# CSI2-ZCU106-EVK-2_Rev01.net
KiCad netlist of a schematic drawn in Altium Designer
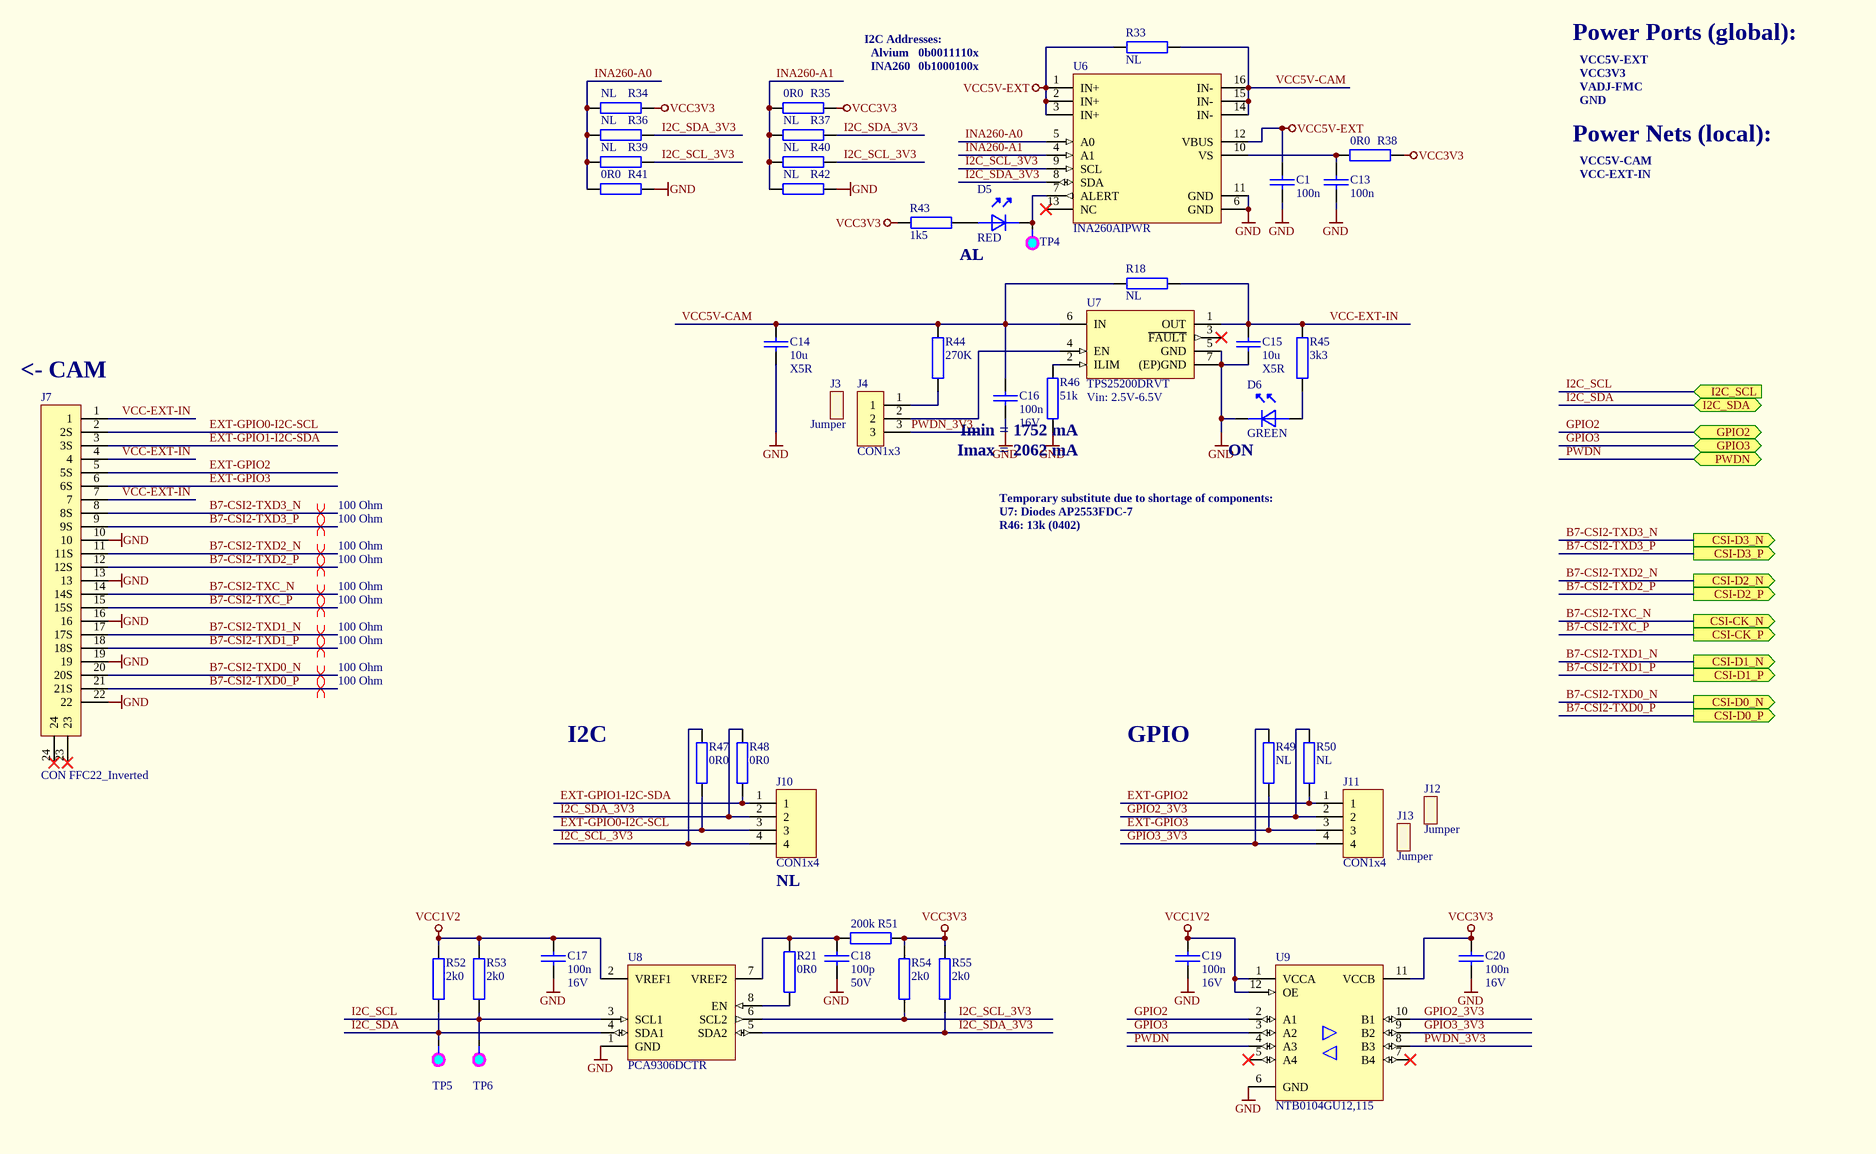
[diagram p0: CSI2-ZCU106-EVK-2_Rev01.SchDoc]

(export (version "E")
  (design (tool "Eeschema 10.0.6"))
  (components
    (comp (ref "C1")
      (value "100n")
      (footprint "C-0402_0.55")
      (description "Capacitor Ceramic SMD/0402/16V/X7R/10%")
      (fields (field (name "KHK PART NUMBER") "K8340114") (field (name "MANUFACTURER") "several"))
      (libsource (lib "AVT_KHK_Lib") (part "C 100N 10% 16V X7R 402"))
    )
    (comp (ref "C13")
      (value "100n")
      (footprint "C-0402_0.55")
      (description "Capacitor Ceramic SMD/0402/16V/X7R/10%")
      (fields (field (name "KHK PART NUMBER") "K8340114") (field (name "MANUFACTURER") "several"))
      (libsource (lib "AVT_KHK_Lib") (part "C 100N 10% 16V X7R 402"))
    )
    (comp (ref "C14")
      (value "10u")
      (footprint "C-0805_1.4")
      (description "Capacitor Ceramic SMD/0805/16V/X5R/10%")
      (fields
        (field (name "KHK PART NUMBER") "K8340151")
        (field (name "MANUFACTURER") "several")
        (field (name "DIELECTRIC") "X5R")
      )
      (libsource (lib "AVT_KHK_Lib") (part "C 10U 16V X5R 0805"))
    )
    (comp (ref "C15")
      (value "10u")
      (footprint "C-0805_1.4")
      (description "Capacitor Ceramic SMD/0805/16V/X5R/10%")
      (fields
        (field (name "KHK PART NUMBER") "K8340151")
        (field (name "MANUFACTURER") "several")
        (field (name "DIELECTRIC") "X5R")
      )
      (libsource (lib "AVT_KHK_Lib") (part "C 10U 16V X5R 0805"))
    )
    (comp (ref "C16")
      (value "100n")
      (footprint "C-0402_0.55")
      (description "Capacitor Ceramic SMD/0402/16V/X7R/10%")
      (fields
        (field (name "KHK PART NUMBER") "K8340114")
        (field (name "MANUFACTURER") "several")
        (field (name "VOLTAGE") "16V")
      )
      (libsource (lib "AVT_KHK_Lib") (part "C 100N 10% 16V X7R 402"))
    )
    (comp (ref "C17")
      (value "100n")
      (footprint "C-0402_0.55")
      (description "Capacitor Ceramic SMD/0402/16V/X7R/10%")
      (fields
        (field (name "KHK PART NUMBER") "K8340114")
        (field (name "MANUFACTURER") "several")
        (field (name "VOLTAGE") "16V")
      )
      (libsource (lib "AVT_KHK_Lib") (part "C 100N 10% 16V X7R 402"))
    )
    (comp (ref "C18")
      (value "100p")
      (footprint "C-0402_0.55")
      (description "Capacitor Ceramic SMD/0402/50V/X7R/10%")
      (fields
        (field (name "KHK PART NUMBER") "K8340145")
        (field (name "MANUFACTURER") "several")
        (field (name "VOLTAGE") "50V")
      )
      (libsource (lib "AVT_KHK_Lib") (part "C 100P 50V X7R 0402"))
    )
    (comp (ref "C19")
      (value "100n")
      (footprint "C-0402_0.55")
      (description "Capacitor Ceramic SMD/0402/16V/X7R/10%")
      (fields
        (field (name "KHK PART NUMBER") "K8340114")
        (field (name "MANUFACTURER") "several")
        (field (name "VOLTAGE") "16V")
      )
      (libsource (lib "AVT_KHK_Lib") (part "C 100N 10% 16V X7R 402"))
    )
    (comp (ref "C20")
      (value "100n")
      (footprint "C-0402_0.55")
      (description "Capacitor Ceramic SMD/0402/16V/X7R/10%")
      (fields
        (field (name "KHK PART NUMBER") "K8340114")
        (field (name "MANUFACTURER") "several")
        (field (name "VOLTAGE") "16V")
      )
      (libsource (lib "AVT_KHK_Lib") (part "C 100N 10% 16V X7R 402"))
    )
    (comp (ref "D5")
      (value "RED")
      (footprint "D-0603-LED")
      (description "Chip LED red 250mcd")
      (fields (field (name "KHK PART NUMBER") "8145") (field (name "MANUFACTURER") "Würth"))
      (libsource (lib "AVT_KHK_Lib") (part "D LED 0603 red"))
    )
    (comp (ref "D6")
      (value "GREEN")
      (footprint "D-0603-LED")
      (description "Chip LED green 430mcd")
      (fields (field (name "KHK PART NUMBER") "8172") (field (name "MANUFACTURER") "Würth"))
      (libsource (lib "AVT_KHK_Lib") (part "D LED 0603 green"))
    )
    (comp (ref "J3")
      (value "Jumper")
      (footprint "J-JUMPER-2.54")
      (description "CON/JUMPER/STC02SYAN; 2-pin; 2.54mm; 3A; FEMALE; VERTICAL; BLACK")
      (fields (field (name "KHK PART NUMBER") "13444") (field (name "MANUFACTURER") "several"))
      (libsource (lib "") (part "CON Jumper 2.54mm_1"))
    )
    (comp (ref "J4")
      (value "CON1x3")
      (footprint "CON 1x3 RM2.54")
      (fields (field (name "MANUFACTURER") "several") (field (name "KHK PART NUMBER") "15338"))
      (libsource (lib "Connector") (part "CON 1x3 2.54 several"))
    )
    (comp (ref "J7")
      (value "CON FFC22_Inverted")
      (footprint "J-FH55-22S-0.5SH - Inverted Pins")
      (description "FFC Connector 0.5mm shielded")
      (fields
        (field (name "KHK PART NUMBER") "10357")
        (field (name "MANUFACTURER PART NUMBER") "FH55-22S-0.5SH")
      )
      (libsource (lib "AVT_KHK_Lib") (part "CON FFC22_FH55-22S-0.5SH_Inverted"))
    )
    (comp (ref "J10")
      (value "CON1x4")
      (footprint "CON 1x4 RM2.54")
      (fields (field (name "MANUFACTURER") "several") (field (name "KHK PART NUMBER") "15343"))
      (libsource (lib "Connector") (part "CON 1x4 2.54 several"))
    )
    (comp (ref "J11")
      (value "CON1x4")
      (footprint "CON 1x4 RM2.54")
      (fields (field (name "MANUFACTURER") "several") (field (name "KHK PART NUMBER") "15343"))
      (libsource (lib "Connector") (part "CON 1x4 2.54 several"))
    )
    (comp (ref "J12")
      (value "Jumper")
      (footprint "J-JUMPER-2.54")
      (description "CON/JUMPER/STC02SYAN; 2-pin; 2.54mm; 3A; FEMALE; VERTICAL; BLACK")
      (fields (field (name "KHK PART NUMBER") "13444") (field (name "MANUFACTURER") "several"))
      (libsource (lib "AVT_KHK_Lib") (part "CON Jumper 2.54mm"))
    )
    (comp (ref "J13")
      (value "Jumper")
      (footprint "J-JUMPER-2.54")
      (description "CON/JUMPER/STC02SYAN; 2-pin; 2.54mm; 3A; FEMALE; VERTICAL; BLACK")
      (fields (field (name "KHK PART NUMBER") "13444") (field (name "MANUFACTURER") "several"))
      (libsource (lib "AVT_KHK_Lib") (part "CON Jumper 2.54mm"))
    )
    (comp (ref "R18")
      (value "NL")
      (footprint "R-0603_0.6")
      (description "Standard Resistor SMD/0603/1%/100mW/TK200")
      (fields (field (name "TOLERANCE") "1%"))
      (libsource (lib "AVT_KHK_Lib") (part "R X 0603"))
    )
    (comp (ref "R21")
      (value "0R0")
      (footprint "R-0603_0.6")
      (description "Standard Resistor SMD/0603/1%/100mW/TK200")
      (fields (field (name "KHK PART NUMBER") "K8250041") (field (name "MANUFACTURER") "several"))
      (libsource (lib "AVT_KHK_Lib") (part "R 0R0 1% 0603"))
    )
    (comp (ref "R33")
      (value "NL")
      (footprint "R-0603_0.6")
      (description "Standard Resistor SMD/0603/1%/100mW/TK200")
      (fields (field (name "TOLERANCE") "1%"))
      (libsource (lib "AVT_KHK_Lib") (part "R X 0603"))
    )
    (comp (ref "R34")
      (value "NL")
      (footprint "R-0603_0.6")
      (description "Standard Resistor SMD/0603/1%/100mW/TK200")
      (fields (field (name "TOLERANCE") "1%"))
      (libsource (lib "AVT_KHK_Lib") (part "R X 0603"))
    )
    (comp (ref "R35")
      (value "0R0")
      (footprint "R-0603_0.6")
      (description "Standard Resistor SMD/0603/1%/100mW/TK200")
      (fields (field (name "KHK PART NUMBER") "K8250041") (field (name "MANUFACTURER") "several"))
      (libsource (lib "AVT_KHK_Lib") (part "R 0R0 1% 0603"))
    )
    (comp (ref "R36")
      (value "NL")
      (footprint "R-0603_0.6")
      (description "Standard Resistor SMD/0603/1%/100mW/TK200")
      (fields (field (name "TOLERANCE") "1%"))
      (libsource (lib "AVT_KHK_Lib") (part "R X 0603"))
    )
    (comp (ref "R37")
      (value "NL")
      (footprint "R-0603_0.6")
      (description "Standard Resistor SMD/0603/1%/100mW/TK200")
      (fields (field (name "TOLERANCE") "1%"))
      (libsource (lib "AVT_KHK_Lib") (part "R X 0603"))
    )
    (comp (ref "R38")
      (value "0R0")
      (footprint "R-0603_0.6")
      (description "Standard Resistor SMD/0603/1%/100mW/TK200")
      (fields (field (name "KHK PART NUMBER") "K8250041") (field (name "MANUFACTURER") "several"))
      (libsource (lib "AVT_KHK_Lib") (part "R 0R0 1% 0603"))
    )
    (comp (ref "R39")
      (value "NL")
      (footprint "R-0603_0.6")
      (description "Standard Resistor SMD/0603/1%/100mW/TK200")
      (fields (field (name "TOLERANCE") "1%"))
      (libsource (lib "AVT_KHK_Lib") (part "R X 0603"))
    )
    (comp (ref "R40")
      (value "NL")
      (footprint "R-0603_0.6")
      (description "Standard Resistor SMD/0603/1%/100mW/TK200")
      (fields (field (name "TOLERANCE") "1%"))
      (libsource (lib "AVT_KHK_Lib") (part "R X 0603"))
    )
    (comp (ref "R41")
      (value "0R0")
      (footprint "R-0603_0.6")
      (description "Standard Resistor SMD/0603/1%/100mW/TK200")
      (fields (field (name "KHK PART NUMBER") "K8250041") (field (name "MANUFACTURER") "several"))
      (libsource (lib "AVT_KHK_Lib") (part "R 0R0 1% 0603"))
    )
    (comp (ref "R42")
      (value "NL")
      (footprint "R-0603_0.6")
      (description "Standard Resistor SMD/0603/1%/100mW/TK200")
      (fields (field (name "TOLERANCE") "1%"))
      (libsource (lib "AVT_KHK_Lib") (part "R X 0603"))
    )
    (comp (ref "R43")
      (value "1k5")
      (footprint "R-0402_0.4")
      (description "Standard Resistor SMD/0402/1%/63mW/TK100")
      (fields (field (name "KHK PART NUMBER") "K8250358") (field (name "MANUFACTURER") "several"))
      (libsource (lib "AVT_KHK_Lib") (part "R 1K5 1% 0402"))
    )
    (comp (ref "R44")
      (value "270K")
      (footprint "R-0402_0.4")
      (description "Standard Resistor SMD/0402/1%/63mW/TK100")
      (fields (field (name "KHK PART NUMBER") "3875") (field (name "MANUFACTURER") "several"))
      (libsource (lib "AVT_KHK_Lib") (part "R 270K 1% 0402"))
    )
    (comp (ref "R45")
      (value "3k3")
      (footprint "R-0402_0.4")
      (description "Standard Resistor SMD/0402/1%/63mW/TK100")
      (fields (field (name "KHK PART NUMBER") "K8250347") (field (name "MANUFACTURER") "several"))
      (libsource (lib "AVT_KHK_Lib") (part "R 3k3 1% 0402"))
    )
    (comp (ref "R46")
      (value "51k")
      (footprint "R-0402_0.4")
      (description "Standard Resistor SMD/0402/1%/63mW/TK100")
      (fields (field (name "KHK PART NUMBER") "K8250273") (field (name "MANUFACTURER") "several"))
      (libsource (lib "AVT_KHK_Lib") (part "R 51K 1% 0402"))
    )
    (comp (ref "R47")
      (value "0R0")
      (footprint "R-0603_0.6")
      (description "Standard Resistor SMD/0603/1%/100mW/TK200")
      (fields (field (name "KHK PART NUMBER") "K8250041") (field (name "MANUFACTURER") "several"))
      (libsource (lib "AVT_KHK_Lib") (part "R 0R0 1% 0603"))
    )
    (comp (ref "R48")
      (value "0R0")
      (footprint "R-0603_0.6")
      (description "Standard Resistor SMD/0603/1%/100mW/TK200")
      (fields (field (name "KHK PART NUMBER") "K8250041") (field (name "MANUFACTURER") "several"))
      (libsource (lib "AVT_KHK_Lib") (part "R 0R0 1% 0603"))
    )
    (comp (ref "R49")
      (value "NL")
      (footprint "R-0603_0.6")
      (description "Standard Resistor SMD/0603/1%/100mW/TK200")
      (fields (field (name "TOLERANCE") "1%"))
      (libsource (lib "AVT_KHK_Lib") (part "R X 0603"))
    )
    (comp (ref "R50")
      (value "NL")
      (footprint "R-0603_0.6")
      (description "Standard Resistor SMD/0603/1%/100mW/TK200")
      (fields (field (name "TOLERANCE") "1%"))
      (libsource (lib "AVT_KHK_Lib") (part "R X 0603"))
    )
    (comp (ref "R51")
      (value "200k")
      (footprint "R-0402_0.4")
      (description "Standard Resistor SMD/0402/1%/63mW/TK100")
      (fields (field (name "KHK PART NUMBER") "K8250280") (field (name "MANUFACTURER") "several"))
      (libsource (lib "AVT_KHK_Lib") (part "R 200K 1% 0402"))
    )
    (comp (ref "R52")
      (value "2k0")
      (footprint "R-0402_0.4")
      (description "Standard Resistor SMD/0402/1%/63mW/TK100")
      (fields (field (name "KHK PART NUMBER") "K8250311") (field (name "MANUFACTURER") "several"))
      (libsource (lib "AVT_KHK_Lib") (part "R 2k0 1% 0402"))
    )
    (comp (ref "R53")
      (value "2k0")
      (footprint "R-0402_0.4")
      (description "Standard Resistor SMD/0402/1%/63mW/TK100")
      (fields (field (name "KHK PART NUMBER") "K8250311") (field (name "MANUFACTURER") "several"))
      (libsource (lib "AVT_KHK_Lib") (part "R 2k0 1% 0402"))
    )
    (comp (ref "R54")
      (value "2k0")
      (footprint "R-0402_0.4")
      (description "Standard Resistor SMD/0402/1%/63mW/TK100")
      (fields (field (name "KHK PART NUMBER") "K8250311") (field (name "MANUFACTURER") "several"))
      (libsource (lib "AVT_KHK_Lib") (part "R 2k0 1% 0402"))
    )
    (comp (ref "R55")
      (value "2k0")
      (footprint "R-0402_0.4")
      (description "Standard Resistor SMD/0402/1%/63mW/TK100")
      (fields (field (name "KHK PART NUMBER") "K8250311") (field (name "MANUFACTURER") "several"))
      (libsource (lib "AVT_KHK_Lib") (part "R 2k0 1% 0402"))
    )
    (comp (ref "TP4")
      (value "TP")
      (footprint "TP_16_10")
      (description "Testpoint: Pad=1,6mm; Hole=1,0mm")
      (libsource (lib "AVT_KHK_Lib") (part "TP_16_10"))
    )
    (comp (ref "TP5")
      (value "TP")
      (footprint "TP_16_10")
      (description "Testpoint: Pad=1,6mm; Hole=1,0mm")
      (libsource (lib "AVT_KHK_Lib") (part "TP_16_10"))
    )
    (comp (ref "TP6")
      (value "TP")
      (footprint "TP_16_10")
      (description "Testpoint: Pad=1,6mm; Hole=1,0mm")
      (libsource (lib "AVT_KHK_Lib") (part "TP_16_10"))
    )
    (comp (ref "U6")
      (value "INA260AIPWR")
      (footprint "IC-TSSOP16 6.4x5.1x1.2")
      (description "IC/PWR/CURR SHUNT MONITOR/2.7-5.5V;4.5mR/TSSOP16/5.0x4.4x1.2mm")
      (fields (field (name "MANUFACTURER") "TI"))
      (libsource (lib "AVT_KHK_Lib") (part "IC INA260"))
    )
    (comp (ref "U7")
      (value "TPS25200DRVT")
      (footprint "IC-DFN06_2.0x2.0x0.8")
      (description "IC/PWR/LOADSW;2V5-6V5;2A5;0R099/6-WDFN/2x2x0.8mm")
      (fields
        (field (name "KHK PART NUMBER") "14277")
        (field (name "MANUFACTURER") "Texas Instruments")
        (field (name "VIN") "2.5V-6.5V")
      )
      (libsource (lib "AVT_KHK_Lib") (part "IC  TPS25200DRVT"))
    )
    (comp (ref "U8")
      (value "PCA9306DCTR")
      (footprint "IC-TSSOP8_3.15x4.25x1.3")
      (description "IC/LOGIC/LEVELSHIFTER;I2C;AUTO-DIR;1V2-5V/SSOP-8/4.25x3.15x1.3mm")
      (fields (field (name "KHK PART NUMBER") "9555") (field (name "MANUFACTURER") "TI"))
      (libsource (lib "AVT_KHK_Lib") (part "IC PCA9306DCTR"))
    )
    (comp (ref "U9")
      (value "NTB0104GU12,115")
      (footprint "IC-XQFN12_1.7x2x0.5")
      (description "IC/LOGIC/Levelshifter;Auto-Dir;Bidirectional;Push-Pull;-40-+125°C/")
      (fields (field (name "MANUFACTURER") "NXP") (field (name "KHK PART NUMBER") "14383"))
      (libsource (lib "AVT_KHK_Lib") (part "IC NTB0104GU12,115"))
    )
  )
  (nets
    (net (code "1") (name "/B7-CSI2-TXC_N") (class "Default")
      (node (ref "J7") (pin "14") (pinfunction "14S_14") (pintype "passive"))
    )
    (net (code "2") (name "/B7-CSI2-TXC_P") (class "Default")
      (node (ref "J7") (pin "15") (pinfunction "15S_15") (pintype "passive"))
    )
    (net (code "3") (name "/B7-CSI2-TXD0_N") (class "Default")
      (node (ref "J7") (pin "20") (pinfunction "20S_20") (pintype "passive"))
    )
    (net (code "4") (name "/B7-CSI2-TXD0_P") (class "Default")
      (node (ref "J7") (pin "21") (pinfunction "21S_21") (pintype "passive"))
    )
    (net (code "5") (name "/B7-CSI2-TXD1_N") (class "Default")
      (node (ref "J7") (pin "17") (pinfunction "17S_17") (pintype "passive"))
    )
    (net (code "6") (name "/B7-CSI2-TXD1_P") (class "Default")
      (node (ref "J7") (pin "18") (pinfunction "18S_18") (pintype "passive"))
    )
    (net (code "7") (name "/B7-CSI2-TXD2_N") (class "Default")
      (node (ref "J7") (pin "11") (pinfunction "11S_11") (pintype "passive"))
    )
    (net (code "8") (name "/B7-CSI2-TXD2_P") (class "Default")
      (node (ref "J7") (pin "12") (pinfunction "12S_12") (pintype "passive"))
    )
    (net (code "9") (name "/B7-CSI2-TXD3_N") (class "Default")
      (node (ref "J7") (pin "8") (pinfunction "8S_8") (pintype "passive"))
    )
    (net (code "10") (name "/B7-CSI2-TXD3_P") (class "Default")
      (node (ref "J7") (pin "9") (pinfunction "9S_9") (pintype "passive"))
    )
    (net (code "11") (name "/EXT-GPIO0-I2C-SCL") (class "Default")
      (node (ref "J10") (pin "3") (pinfunction "3_3") (pintype "passive"))
      (node (ref "J7") (pin "2") (pinfunction "2S_2") (pintype "passive"))
      (node (ref "R47") (pin "1") (pinfunction "1_1") (pintype "passive"))
    )
    (net (code "12") (name "/EXT-GPIO1-I2C-SDA") (class "Default")
      (node (ref "J10") (pin "1") (pinfunction "1_1") (pintype "passive"))
      (node (ref "J7") (pin "3") (pinfunction "3S_3") (pintype "passive"))
      (node (ref "R48") (pin "1") (pinfunction "1_1") (pintype "passive"))
    )
    (net (code "13") (name "/EXT-GPIO2") (class "Default")
      (node (ref "J11") (pin "1") (pinfunction "1_1") (pintype "passive"))
      (node (ref "J7") (pin "5") (pinfunction "5S_5") (pintype "passive"))
      (node (ref "R50") (pin "1") (pinfunction "1_1") (pintype "passive"))
    )
    (net (code "14") (name "/EXT-GPIO3") (class "Default")
      (node (ref "J11") (pin "3") (pinfunction "3_3") (pintype "passive"))
      (node (ref "J7") (pin "6") (pinfunction "6S_6") (pintype "passive"))
      (node (ref "R49") (pin "1") (pinfunction "1_1") (pintype "passive"))
    )
    (net (code "15") (name "/GPIO2") (class "Default")
      (node (ref "U9") (pin "2") (pinfunction "A1_2") (pintype "bidirectional"))
    )
    (net (code "16") (name "/GPIO2_3V3") (class "Default")
      (node (ref "J11") (pin "2") (pinfunction "2_2") (pintype "passive"))
      (node (ref "R50") (pin "2") (pinfunction "2_2") (pintype "passive"))
      (node (ref "U9") (pin "10") (pinfunction "B1_10") (pintype "bidirectional"))
    )
    (net (code "17") (name "/GPIO3") (class "Default")
      (node (ref "U9") (pin "3") (pinfunction "A2_3") (pintype "bidirectional"))
    )
    (net (code "18") (name "/GPIO3_3V3") (class "Default")
      (node (ref "J11") (pin "4") (pinfunction "4_4") (pintype "passive"))
      (node (ref "R49") (pin "2") (pinfunction "2_2") (pintype "passive"))
      (node (ref "U9") (pin "9") (pinfunction "B2_9") (pintype "bidirectional"))
    )
    (net (code "19") (name "/I2C_SCL") (class "Default")
      (node (ref "R53") (pin "2") (pinfunction "2_2") (pintype "passive"))
      (node (ref "TP6") (pin "1") (pinfunction "1_1") (pintype "passive"))
      (node (ref "U8") (pin "3") (pinfunction "SCL1_3") (pintype "input"))
    )
    (net (code "20") (name "/I2C_SCL_3V3") (class "Default")
      (node (ref "J10") (pin "4") (pinfunction "4_4") (pintype "passive"))
      (node (ref "R39") (pin "1") (pinfunction "1_1") (pintype "passive"))
      (node (ref "R40") (pin "1") (pinfunction "1_1") (pintype "passive"))
      (node (ref "R47") (pin "2") (pinfunction "2_2") (pintype "passive"))
      (node (ref "R54") (pin "1") (pinfunction "1_1") (pintype "passive"))
      (node (ref "U6") (pin "9") (pinfunction "SCL_9") (pintype "input"))
      (node (ref "U8") (pin "6") (pinfunction "SCL2_6") (pintype "output"))
    )
    (net (code "21") (name "/I2C_SDA") (class "Default")
      (node (ref "R52") (pin "2") (pinfunction "2_2") (pintype "passive"))
      (node (ref "TP5") (pin "1") (pinfunction "1_1") (pintype "passive"))
      (node (ref "U8") (pin "4") (pinfunction "SDA1_4") (pintype "bidirectional"))
    )
    (net (code "22") (name "/I2C_SDA_3V3") (class "Default")
      (node (ref "J10") (pin "2") (pinfunction "2_2") (pintype "passive"))
      (node (ref "R36") (pin "1") (pinfunction "1_1") (pintype "passive"))
      (node (ref "R37") (pin "1") (pinfunction "1_1") (pintype "passive"))
      (node (ref "R48") (pin "2") (pinfunction "2_2") (pintype "passive"))
      (node (ref "R55") (pin "1") (pinfunction "1_1") (pintype "passive"))
      (node (ref "U6") (pin "8") (pinfunction "SDA_8") (pintype "bidirectional"))
      (node (ref "U8") (pin "5") (pinfunction "SDA2_5") (pintype "bidirectional"))
    )
    (net (code "23") (name "/INA260-A0") (class "Default")
      (node (ref "R34") (pin "2") (pinfunction "2_2") (pintype "passive"))
      (node (ref "R36") (pin "2") (pinfunction "2_2") (pintype "passive"))
      (node (ref "R39") (pin "2") (pinfunction "2_2") (pintype "passive"))
      (node (ref "R41") (pin "2") (pinfunction "2_2") (pintype "passive"))
      (node (ref "U6") (pin "5") (pinfunction "A0_5") (pintype "input"))
    )
    (net (code "24") (name "/INA260-A1") (class "Default")
      (node (ref "R35") (pin "2") (pinfunction "2_2") (pintype "passive"))
      (node (ref "R37") (pin "2") (pinfunction "2_2") (pintype "passive"))
      (node (ref "R40") (pin "2") (pinfunction "2_2") (pintype "passive"))
      (node (ref "R42") (pin "2") (pinfunction "2_2") (pintype "passive"))
      (node (ref "U6") (pin "4") (pinfunction "A1_4") (pintype "input"))
    )
    (net (code "25") (name "/PWDN") (class "Default")
      (node (ref "U9") (pin "4") (pinfunction "A3_4") (pintype "bidirectional"))
    )
    (net (code "26") (name "/PWDN_3V3") (class "Default")
      (node (ref "J4") (pin "3") (pinfunction "3_3") (pintype "passive"))
      (node (ref "U9") (pin "8") (pinfunction "B3_8") (pintype "bidirectional"))
    )
    (net (code "27") (name "/VCC-EXT-IN") (class "Default")
      (node (ref "C15") (pin "1") (pinfunction "1_1") (pintype "passive"))
      (node (ref "J7") (pin "1") (pinfunction "1_1") (pintype "passive"))
      (node (ref "J7") (pin "4") (pinfunction "4_4") (pintype "passive"))
      (node (ref "J7") (pin "7") (pinfunction "7_7") (pintype "passive"))
      (node (ref "R18") (pin "1") (pinfunction "1_1") (pintype "passive"))
      (node (ref "R45") (pin "1") (pinfunction "1_1") (pintype "passive"))
      (node (ref "U7") (pin "1") (pinfunction "OUT_1") (pintype "power_in"))
    )
    (net (code "28") (name "/VCC5V-CAM") (class "Default")
      (node (ref "C14") (pin "1") (pinfunction "1_1") (pintype "passive"))
      (node (ref "C16") (pin "1") (pinfunction "1_1") (pintype "passive"))
      (node (ref "R18") (pin "2") (pinfunction "2_2") (pintype "passive"))
      (node (ref "R33") (pin "1") (pinfunction "1_1") (pintype "passive"))
      (node (ref "R44") (pin "1") (pinfunction "1_1") (pintype "passive"))
      (node (ref "U6") (pin "14") (pinfunction "IN-_14") (pintype "passive"))
      (node (ref "U6") (pin "15") (pinfunction "IN-_15") (pintype "passive"))
      (node (ref "U6") (pin "16") (pinfunction "IN-_16") (pintype "passive"))
      (node (ref "U7") (pin "6") (pinfunction "IN_6") (pintype "power_in"))
    )
    (net (code "29") (name "GND") (class "Default")
      (node (ref "C1") (pin "2") (pinfunction "2_2") (pintype "passive"))
      (node (ref "C13") (pin "2") (pinfunction "2_2") (pintype "passive"))
      (node (ref "C14") (pin "2") (pinfunction "2_2") (pintype "passive"))
      (node (ref "C15") (pin "2") (pinfunction "2_2") (pintype "passive"))
      (node (ref "C16") (pin "2") (pinfunction "2_2") (pintype "passive"))
      (node (ref "C17") (pin "2") (pinfunction "2_2") (pintype "passive"))
      (node (ref "C18") (pin "2") (pinfunction "2_2") (pintype "passive"))
      (node (ref "C19") (pin "2") (pinfunction "2_2") (pintype "passive"))
      (node (ref "C20") (pin "2") (pinfunction "2_2") (pintype "passive"))
      (node (ref "D6") (pin "K") (pinfunction "2_K") (pintype "passive"))
      (node (ref "J7") (pin "10") (pinfunction "10_10") (pintype "passive"))
      (node (ref "J7") (pin "13") (pinfunction "13_13") (pintype "passive"))
      (node (ref "J7") (pin "16") (pinfunction "16_16") (pintype "passive"))
      (node (ref "J7") (pin "19") (pinfunction "19_19") (pintype "passive"))
      (node (ref "J7") (pin "22") (pinfunction "22_22") (pintype "passive"))
      (node (ref "R41") (pin "1") (pinfunction "1_1") (pintype "passive"))
      (node (ref "R42") (pin "1") (pinfunction "1_1") (pintype "passive"))
      (node (ref "R46") (pin "1") (pinfunction "1_1") (pintype "passive"))
      (node (ref "U6") (pin "11") (pinfunction "GND_11") (pintype "power_in"))
      (node (ref "U6") (pin "6") (pinfunction "GND_6") (pintype "power_in"))
      (node (ref "U7") (pin "5") (pinfunction "GND_5") (pintype "power_in"))
      (node (ref "U7") (pin "7") (pinfunction "(EP)GND_7") (pintype "power_in"))
      (node (ref "U8") (pin "1") (pinfunction "GND_1") (pintype "power_in"))
      (node (ref "U9") (pin "6") (pinfunction "GND_6") (pintype "power_in"))
    )
    (net (code "30") (name "Net-(D5-1)") (class "Default")
      (node (ref "D5") (pin "A") (pinfunction "1_A") (pintype "passive"))
      (node (ref "R43") (pin "2") (pinfunction "2_2") (pintype "passive"))
    )
    (net (code "31") (name "Net-(D5-2)") (class "Default")
      (node (ref "D5") (pin "K") (pinfunction "2_K") (pintype "passive"))
      (node (ref "TP4") (pin "1") (pinfunction "1_1") (pintype "passive"))
      (node (ref "U6") (pin "7") (pinfunction "ALERT_7") (pintype "output"))
    )
    (net (code "32") (name "Net-(D6-1)") (class "Default")
      (node (ref "D6") (pin "A") (pinfunction "1_A") (pintype "passive"))
      (node (ref "R45") (pin "2") (pinfunction "2_2") (pintype "passive"))
    )
    (net (code "33") (name "Net-(J4-Pad1)") (class "Default")
      (node (ref "J4") (pin "1") (pinfunction "1_1") (pintype "passive"))
      (node (ref "R44") (pin "2") (pinfunction "2_2") (pintype "passive"))
    )
    (net (code "34") (name "Net-(U6-VS)") (class "Default")
      (node (ref "C13") (pin "1") (pinfunction "1_1") (pintype "passive"))
      (node (ref "R38") (pin "2") (pinfunction "2_2") (pintype "passive"))
      (node (ref "U6") (pin "10") (pinfunction "VS_10") (pintype "power_in"))
    )
    (net (code "35") (name "Net-(U7-EN)") (class "Default")
      (node (ref "J4") (pin "2") (pinfunction "2_2") (pintype "passive"))
      (node (ref "U7") (pin "4") (pinfunction "EN_4") (pintype "input"))
    )
    (net (code "36") (name "Net-(U7-ILIM)") (class "Default")
      (node (ref "R46") (pin "2") (pinfunction "2_2") (pintype "passive"))
      (node (ref "U7") (pin "2") (pinfunction "ILIM_2") (pintype "input"))
    )
    (net (code "37") (name "Net-(U8-EN)") (class "Default")
      (node (ref "R21") (pin "2") (pinfunction "2_2") (pintype "passive"))
      (node (ref "U8") (pin "8") (pinfunction "EN_8") (pintype "input"))
    )
    (net (code "38") (name "Net-(U8-VREF2)") (class "Default")
      (node (ref "C18") (pin "1") (pinfunction "1_1") (pintype "passive"))
      (node (ref "R21") (pin "1") (pinfunction "1_1") (pintype "passive"))
      (node (ref "R51") (pin "1") (pinfunction "1_1") (pintype "passive"))
      (node (ref "U8") (pin "7") (pinfunction "VREF2_7") (pintype "power_in"))
    )
    (net (code "39") (name "VCC1V2") (class "Default")
      (node (ref "C17") (pin "1") (pinfunction "1_1") (pintype "passive"))
      (node (ref "C19") (pin "1") (pinfunction "1_1") (pintype "passive"))
      (node (ref "R52") (pin "1") (pinfunction "1_1") (pintype "passive"))
      (node (ref "R53") (pin "1") (pinfunction "1_1") (pintype "passive"))
      (node (ref "U8") (pin "2") (pinfunction "VREF1_2") (pintype "power_in"))
      (node (ref "U9") (pin "1") (pinfunction "VCCA_1") (pintype "power_in"))
      (node (ref "U9") (pin "12") (pinfunction "OE_12") (pintype "input"))
    )
    (net (code "40") (name "VCC3V3") (class "Default")
      (node (ref "C20") (pin "1") (pinfunction "1_1") (pintype "passive"))
      (node (ref "R34") (pin "1") (pinfunction "1_1") (pintype "passive"))
      (node (ref "R35") (pin "1") (pinfunction "1_1") (pintype "passive"))
      (node (ref "R38") (pin "1") (pinfunction "1_1") (pintype "passive"))
      (node (ref "R43") (pin "1") (pinfunction "1_1") (pintype "passive"))
      (node (ref "R51") (pin "2") (pinfunction "2_2") (pintype "passive"))
      (node (ref "R54") (pin "2") (pinfunction "2_2") (pintype "passive"))
      (node (ref "R55") (pin "2") (pinfunction "2_2") (pintype "passive"))
      (node (ref "U9") (pin "11") (pinfunction "VCCB_11") (pintype "power_in"))
    )
    (net (code "41") (name "VCC5V-EXT") (class "Default")
      (node (ref "C1") (pin "1") (pinfunction "1_1") (pintype "passive"))
      (node (ref "R33") (pin "2") (pinfunction "2_2") (pintype "passive"))
      (node (ref "U6") (pin "1") (pinfunction "IN+_1") (pintype "passive"))
      (node (ref "U6") (pin "12") (pinfunction "VBUS_12") (pintype "power_in"))
      (node (ref "U6") (pin "2") (pinfunction "IN+_2") (pintype "passive"))
      (node (ref "U6") (pin "3") (pinfunction "IN+_3") (pintype "passive"))
    )
    (net (code "42") (name "unconnected-(J7-Pad23)") (class "Default")
      (node (ref "J7") (pin "23") (pinfunction "23_23") (pintype "passive+no_connect"))
    )
    (net (code "43") (name "unconnected-(J7-Pad24)") (class "Default")
      (node (ref "J7") (pin "24") (pinfunction "24_24") (pintype "passive+no_connect"))
    )
    (net (code "44") (name "unconnected-(U6-NC-Pad13)") (class "Default")
      (node (ref "U6") (pin "13") (pinfunction "NC_13") (pintype "passive+no_connect"))
    )
    (net (code "45") (name "unconnected-(U7-~{FAULT}-Pad3)") (class "Default")
      (node (ref "U7") (pin "3") (pinfunction "~{FAULT}_3") (pintype "output+no_connect"))
    )
    (net (code "46") (name "unconnected-(U9-A4-Pad5)") (class "Default")
      (node (ref "U9") (pin "5") (pinfunction "A4_5") (pintype "bidirectional+no_connect"))
    )
    (net (code "47") (name "unconnected-(U9-B4-Pad7)") (class "Default")
      (node (ref "U9") (pin "7") (pinfunction "B4_7") (pintype "bidirectional+no_connect"))
    )
  )
)
